# 04_IMU.net
KiCad netlist of a schematic drawn in Altium Designer
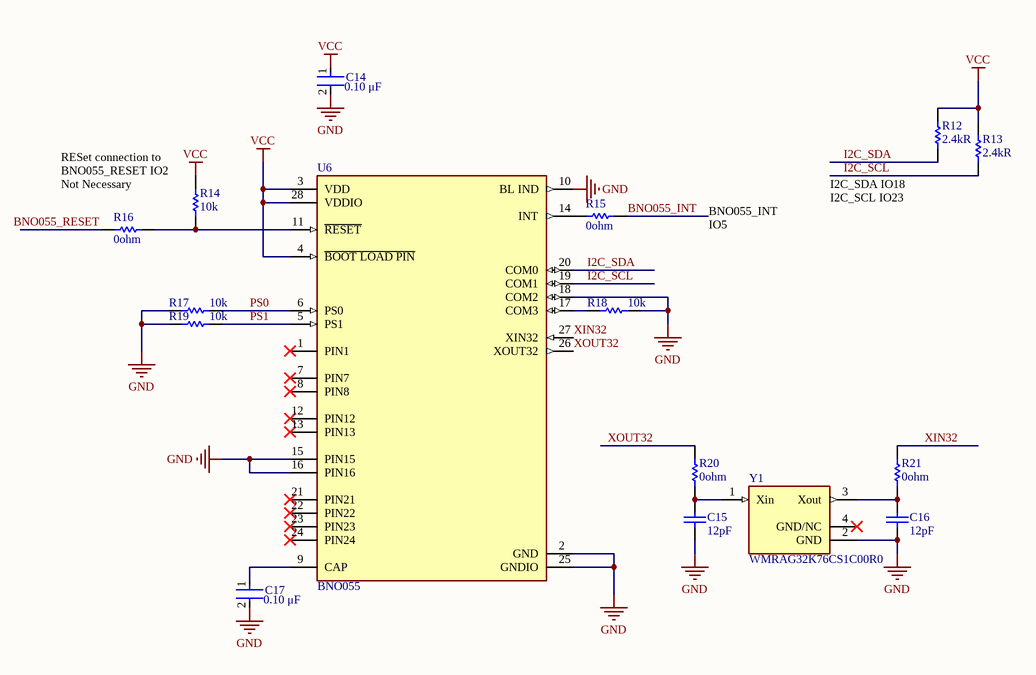
[diagram p0: 04_IMU.SchDoc]

(export (version "E")
  (design (tool "Eeschema 10.0.6"))
  (components
    (comp (ref "C14")
      (value "C0603C104M4RAC7411")
      (footprint "FP-C0603C-CF-MFG")
      (description "CAP CER 0.1UF 16V X7R 0603")
      (fields
        (field (name "TOLERANCE") "0.2")
        (field (name "CAPACITANCE") "0.10 μF")
        (field (name "MANUFACTURER") "KEMET")
      )
      (libsource (lib "Altium Content Vault") (part "b4654b650e69147ec39a6b967a45e02"))
    )
    (comp (ref "C15")
      (value "12pF")
      (footprint "CAPC1608X90X40NL10T20")
      (description "Chip Capacitor, 12 pF, +/- 5%, 50 V, -55 to 125 degC, 0603 (1608 Metric), RoHS, Tape and Reel")
      (fields (field (name "TOLERANCE") "1%") (field (name "Comment") "CC0603JRNPO9BN120"))
      (libsource (lib "Altium Content Vault") (part "CAP-NP-2"))
    )
    (comp (ref "C16")
      (value "12pF")
      (footprint "CAPC1608X90X40NL10T20")
      (description "Chip Capacitor, 12 pF, +/- 5%, 50 V, -55 to 125 degC, 0603 (1608 Metric), RoHS, Tape and Reel")
      (fields (field (name "TOLERANCE") "1%") (field (name "Comment") "CC0603JRNPO9BN120"))
      (libsource (lib "Altium Content Vault") (part "CAP-NP-2"))
    )
    (comp (ref "C17")
      (value "C0603C104M4RAC7411")
      (footprint "FP-C0603C-CF-MFG")
      (description "CAP CER 0.1UF 16V X7R 0603")
      (fields
        (field (name "TOLERANCE") "0.2")
        (field (name "CAPACITANCE") "0.10 μF")
        (field (name "MANUFACTURER") "KEMET")
      )
      (libsource (lib "Altium Content Vault") (part "b4654b650e69147ec39a6b967a45e02"))
    )
    (comp (ref "R12")
      (value "2.4kR")
      (footprint "RESC1608X50X30ML20T20")
      (fields (field (name "PART NUMBER") "RR0816P-242-D") (field (name "MANUFACTURER") "Susumu"))
      (libsource (lib "Altium Content Vault") (part "RES"))
    )
    (comp (ref "R13")
      (value "2.4kR")
      (footprint "RESC1608X50X30ML20T20")
      (fields (field (name "PART NUMBER") "RR0816P-242-D") (field (name "MANUFACTURER") "Susumu"))
      (libsource (lib "Altium Content Vault") (part "RES"))
    )
    (comp (ref "R14")
      (value "10k")
      (footprint "RESC1609X55X30LL15T15")
      (description "Chip Resistor, 10 KOhm, +/- 1%, 0.1 W, -55 to 155 degC, 0603 (1608 Metric), RoHS, Tape and Reel")
      (fields (field (name "TOLERANCE") "1%") (field (name "MANUFACTURER") "Panasonic"))
      (libsource (lib "Altium Content Vault") (part "RES-2"))
    )
    (comp (ref "R15")
      (value "0ohm")
      (footprint "RESC1608X55X25ML10T15")
      (description "Chip Resistor, 0 Ohm, +/- 5%, 0.1 W, -55 to 155 degC, 0603 (1608 Metric), RoHS, Tape and Reel")
      (fields (field (name "TOLERANCE") "5%") (field (name "MANUFACTURER") "Yageo"))
      (libsource (lib "Altium Content Vault") (part "RES-2"))
    )
    (comp (ref "R16")
      (value "0ohm")
      (footprint "RESC1608X55X25ML10T15")
      (description "Chip Resistor, 0 Ohm, +/- 5%, 0.1 W, -55 to 155 degC, 0603 (1608 Metric), RoHS, Tape and Reel")
      (fields (field (name "TOLERANCE") "5%") (field (name "MANUFACTURER") "Yageo"))
      (libsource (lib "Altium Content Vault") (part "RES-2"))
    )
    (comp (ref "R17")
      (value "10k")
      (footprint "RESC1609X55X30LL15T15")
      (description "Chip Resistor, 10 KOhm, +/- 1%, 0.1 W, -55 to 155 degC, 0603 (1608 Metric), RoHS, Tape and Reel")
      (fields (field (name "TOLERANCE") "1%") (field (name "MANUFACTURER") "Panasonic"))
      (libsource (lib "Altium Content Vault") (part "RES-2"))
    )
    (comp (ref "R18")
      (value "10k")
      (footprint "RESC1609X55X30LL15T15")
      (description "Chip Resistor, 10 KOhm, +/- 1%, 0.1 W, -55 to 155 degC, 0603 (1608 Metric), RoHS, Tape and Reel")
      (fields (field (name "TOLERANCE") "1%") (field (name "MANUFACTURER") "Panasonic"))
      (libsource (lib "Altium Content Vault") (part "RES-2"))
    )
    (comp (ref "R19")
      (value "10k")
      (footprint "RESC1609X55X30LL15T15")
      (description "Chip Resistor, 10 KOhm, +/- 1%, 0.1 W, -55 to 155 degC, 0603 (1608 Metric), RoHS, Tape and Reel")
      (fields (field (name "TOLERANCE") "1%") (field (name "MANUFACTURER") "Panasonic"))
      (libsource (lib "Altium Content Vault") (part "RES-2"))
    )
    (comp (ref "R20")
      (value "0ohm")
      (footprint "RESC1608X55X25ML10T15")
      (description "Chip Resistor, 0 Ohm, +/- 5%, 0.1 W, -55 to 155 degC, 0603 (1608 Metric), RoHS, Tape and Reel")
      (fields (field (name "TOLERANCE") "5%") (field (name "MANUFACTURER") "Yageo"))
      (libsource (lib "Altium Content Vault") (part "RES-2"))
    )
    (comp (ref "R21")
      (value "0ohm")
      (footprint "RESC1608X55X25ML10T15")
      (description "Chip Resistor, 0 Ohm, +/- 5%, 0.1 W, -55 to 155 degC, 0603 (1608 Metric), RoHS, Tape and Reel")
      (fields (field (name "TOLERANCE") "5%") (field (name "MANUFACTURER") "Yageo"))
      (libsource (lib "Altium Content Vault") (part "RES-2"))
    )
    (comp (ref "U6")
      (value "BNO055")
      (footprint "FP-BNO055-MFG")
      (description "IMU ACCEL/GYRO/MAG I2C 28LGA")
      (fields
        (field (name "OCTOPART") "https://octopart.com/bno055-bosch+sensortec-50309911")
        (field (name "VOLTAGE") "1.7~3.6V")
      )
      (libsource (lib "Altium Content Vault") (part "72d621e61db15910e840a84e68b4f76"))
    )
    (comp (ref "Y1")
      (value "WMRAG32K76CS1C00R0")
      (footprint "FP-WMRAG32K76CS1C00R0-MFG")
      (description "MEMS Resonator")
      (fields (field (name "TOLERANCE") "20ppm") (field (name "MANUFACTURER") "Murata"))
      (libsource (lib "Altium Content Vault") (part "f3e38fa55a21b72a83ee03d0b531324"))
    )
  )
  (nets
    (net (code "1") (name "/BNO055_INT") (class "Default")
      (node (ref "R15") (pin "2") (pinfunction "2_2") (pintype "passive"))
    )
    (net (code "2") (name "/BNO055_RESET") (class "Default")
      (node (ref "R16") (pin "1") (pinfunction "1_1") (pintype "passive"))
    )
    (net (code "3") (name "/I2C_SCL") (class "Default")
      (node (ref "R13") (pin "1") (pinfunction "1_1") (pintype "passive"))
      (node (ref "U6") (pin "19") (pinfunction "COM1_19") (pintype "bidirectional"))
    )
    (net (code "4") (name "/I2C_SDA") (class "Default")
      (node (ref "R12") (pin "1") (pinfunction "1_1") (pintype "passive"))
      (node (ref "U6") (pin "20") (pinfunction "COM0_20") (pintype "bidirectional"))
    )
    (net (code "5") (name "/PS0") (class "Default")
      (node (ref "R17") (pin "2") (pinfunction "2_2") (pintype "passive"))
      (node (ref "U6") (pin "6") (pinfunction "PS0_6") (pintype "input"))
    )
    (net (code "6") (name "/PS1") (class "Default")
      (node (ref "R19") (pin "2") (pinfunction "2_2") (pintype "passive"))
      (node (ref "U6") (pin "5") (pinfunction "PS1_5") (pintype "input"))
    )
    (net (code "7") (name "/XIN32") (class "Default")
      (node (ref "R21") (pin "1") (pinfunction "1_1") (pintype "passive"))
      (node (ref "U6") (pin "27") (pinfunction "XIN32_27") (pintype "input"))
    )
    (net (code "8") (name "/XOUT32") (class "Default")
      (node (ref "R20") (pin "1") (pinfunction "1_1") (pintype "passive"))
      (node (ref "U6") (pin "26") (pinfunction "XOUT32_26") (pintype "output"))
    )
    (net (code "9") (name "GND") (class "Default")
      (node (ref "C14") (pin "2") (pinfunction "2_2") (pintype "passive"))
      (node (ref "C15") (pin "1") (pinfunction "1_1") (pintype "passive"))
      (node (ref "C16") (pin "1") (pinfunction "1_1") (pintype "passive"))
      (node (ref "C17") (pin "2") (pinfunction "2_2") (pintype "passive"))
      (node (ref "R17") (pin "1") (pinfunction "1_1") (pintype "passive"))
      (node (ref "R18") (pin "1") (pinfunction "1_1") (pintype "passive"))
      (node (ref "R19") (pin "1") (pinfunction "1_1") (pintype "passive"))
      (node (ref "U6") (pin "10") (pinfunction "BL_IND_10") (pintype "output"))
      (node (ref "U6") (pin "15") (pinfunction "PIN15_15") (pintype "power_in"))
      (node (ref "U6") (pin "16") (pinfunction "PIN16_16") (pintype "power_in"))
      (node (ref "U6") (pin "18") (pinfunction "COM2_18") (pintype "bidirectional"))
      (node (ref "U6") (pin "2") (pinfunction "GND_2") (pintype "power_in"))
      (node (ref "U6") (pin "25") (pinfunction "GNDIO_25") (pintype "power_in"))
      (node (ref "Y1") (pin "2") (pinfunction "GND_2") (pintype "power_in"))
    )
    (net (code "10") (name "Net-(U6-CAP)") (class "Default")
      (node (ref "C17") (pin "1") (pinfunction "1_1") (pintype "passive"))
      (node (ref "U6") (pin "9") (pinfunction "CAP_9") (pintype "passive"))
    )
    (net (code "11") (name "Net-(U6-COM3)") (class "Default")
      (node (ref "R18") (pin "2") (pinfunction "2_2") (pintype "passive"))
      (node (ref "U6") (pin "17") (pinfunction "COM3_17") (pintype "bidirectional"))
    )
    (net (code "12") (name "Net-(U6-INT)") (class "Default")
      (node (ref "R15") (pin "1") (pinfunction "1_1") (pintype "passive"))
      (node (ref "U6") (pin "14") (pinfunction "INT_14") (pintype "output"))
    )
    (net (code "13") (name "Net-(U6-~{RESET})") (class "Default")
      (node (ref "R14") (pin "1") (pinfunction "1_1") (pintype "passive"))
      (node (ref "R16") (pin "2") (pinfunction "2_2") (pintype "passive"))
      (node (ref "U6") (pin "11") (pinfunction "~{RESET}_11") (pintype "input"))
    )
    (net (code "14") (name "Net-(Y1-Xin)") (class "Default")
      (node (ref "C15") (pin "2") (pinfunction "2_2") (pintype "passive"))
      (node (ref "R20") (pin "2") (pinfunction "2_2") (pintype "passive"))
      (node (ref "Y1") (pin "1") (pinfunction "Xin_1") (pintype "input"))
    )
    (net (code "15") (name "Net-(Y1-Xout)") (class "Default")
      (node (ref "C16") (pin "2") (pinfunction "2_2") (pintype "passive"))
      (node (ref "R21") (pin "2") (pinfunction "2_2") (pintype "passive"))
      (node (ref "Y1") (pin "3") (pinfunction "Xout_3") (pintype "output"))
    )
    (net (code "16") (name "VCC") (class "Default")
      (node (ref "C14") (pin "1") (pinfunction "1_1") (pintype "passive"))
      (node (ref "R12") (pin "2") (pinfunction "2_2") (pintype "passive"))
      (node (ref "R13") (pin "2") (pinfunction "2_2") (pintype "passive"))
      (node (ref "R14") (pin "2") (pinfunction "2_2") (pintype "passive"))
      (node (ref "U6") (pin "28") (pinfunction "VDDIO_28") (pintype "power_in"))
      (node (ref "U6") (pin "3") (pinfunction "VDD_3") (pintype "power_in"))
      (node (ref "U6") (pin "4") (pinfunction "~{BOOT_LOAD_PIN}_4") (pintype "input"))
    )
    (net (code "17") (name "unconnected-(U6-PIN1-Pad1)") (class "Default")
      (node (ref "U6") (pin "1") (pinfunction "PIN1_1") (pintype "passive+no_connect"))
    )
    (net (code "18") (name "unconnected-(U6-PIN7-Pad7)") (class "Default")
      (node (ref "U6") (pin "7") (pinfunction "PIN7_7") (pintype "passive+no_connect"))
    )
    (net (code "19") (name "unconnected-(U6-PIN8-Pad8)") (class "Default")
      (node (ref "U6") (pin "8") (pinfunction "PIN8_8") (pintype "passive+no_connect"))
    )
    (net (code "20") (name "unconnected-(U6-PIN12-Pad12)") (class "Default")
      (node (ref "U6") (pin "12") (pinfunction "PIN12_12") (pintype "passive+no_connect"))
    )
    (net (code "21") (name "unconnected-(U6-PIN13-Pad13)") (class "Default")
      (node (ref "U6") (pin "13") (pinfunction "PIN13_13") (pintype "passive+no_connect"))
    )
    (net (code "22") (name "unconnected-(U6-PIN21-Pad21)") (class "Default")
      (node (ref "U6") (pin "21") (pinfunction "PIN21_21") (pintype "passive+no_connect"))
    )
    (net (code "23") (name "unconnected-(U6-PIN22-Pad22)") (class "Default")
      (node (ref "U6") (pin "22") (pinfunction "PIN22_22") (pintype "passive+no_connect"))
    )
    (net (code "24") (name "unconnected-(U6-PIN23-Pad23)") (class "Default")
      (node (ref "U6") (pin "23") (pinfunction "PIN23_23") (pintype "passive+no_connect"))
    )
    (net (code "25") (name "unconnected-(U6-PIN24-Pad24)") (class "Default")
      (node (ref "U6") (pin "24") (pinfunction "PIN24_24") (pintype "passive+no_connect"))
    )
    (net (code "26") (name "unconnected-(Y1-GND{slash}NC-Pad4)") (class "Default")
      (node (ref "Y1") (pin "4") (pinfunction "GND/NC_4") (pintype "passive+no_connect"))
    )
  )
)
